# card.net
KiCad netlist of a schematic drawn in EAGLE
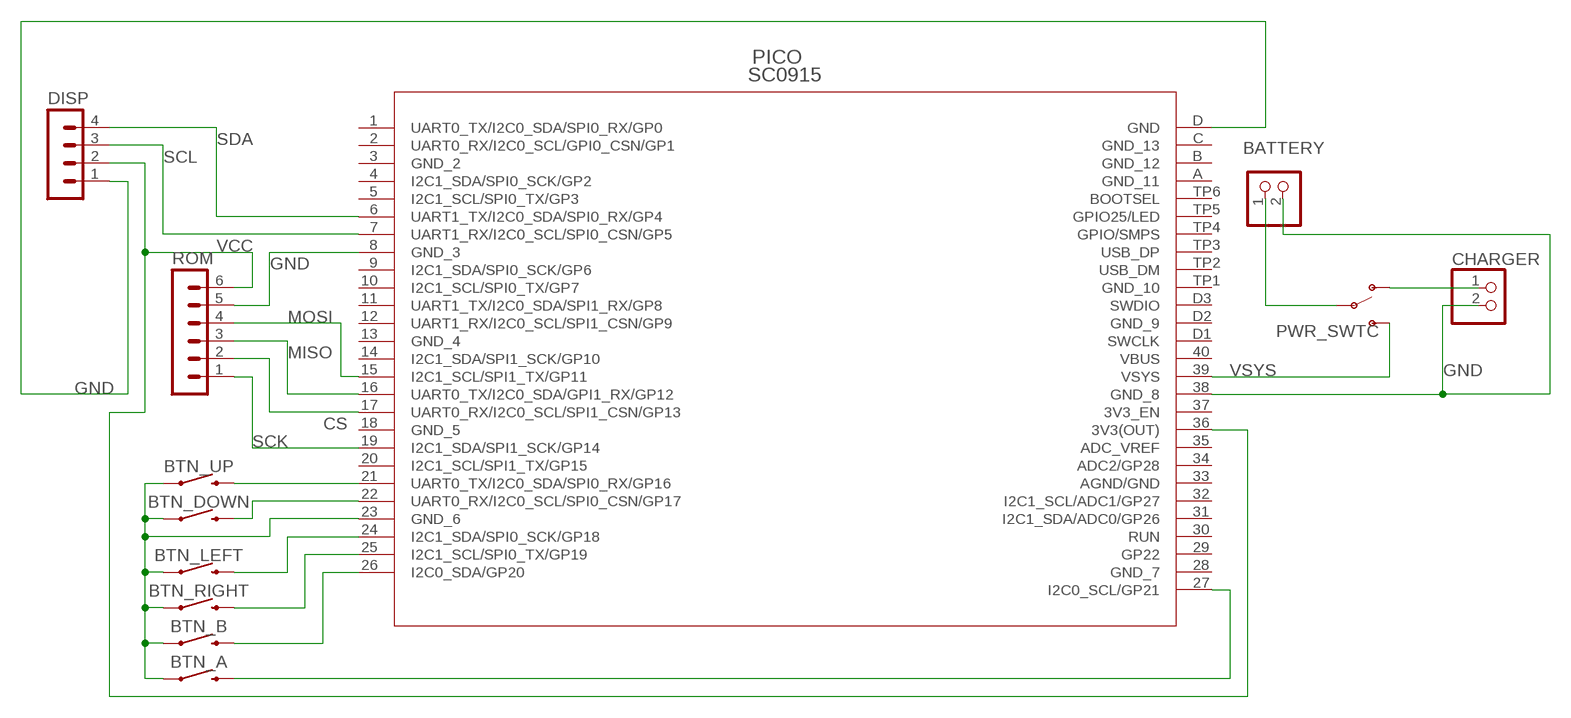
[diagram p0: schematic, sheet 1]

(export (version "E")
  (design (tool "Eeschema 10.0.6"))
  (components
    (comp (ref "BATTERY")
      (value "PINHD-1X2")
      (footprint "eagle-import:1X02")
      (libsource (lib "eagle-import") (part "PINHD-1X2"))
    )
    (comp (ref "BTN_A")
      (value "MOMENTARY-SWITCH-SPST-PTH-6.0MM")
      (footprint "eagle-import:TACTILE_SWITCH_PTH_6.0MM")
      (libsource (lib "eagle-import") (part "MOMENTARY-SWITCH-SPST-PTH-6.0MM"))
    )
    (comp (ref "BTN_B")
      (value "MOMENTARY-SWITCH-SPST-PTH-6.0MM")
      (footprint "eagle-import:TACTILE_SWITCH_PTH_6.0MM")
      (libsource (lib "eagle-import") (part "MOMENTARY-SWITCH-SPST-PTH-6.0MM"))
    )
    (comp (ref "BTN_DOWN")
      (value "MOMENTARY-SWITCH-SPST-PTH-6.0MM")
      (footprint "eagle-import:TACTILE_SWITCH_PTH_6.0MM")
      (libsource (lib "eagle-import") (part "MOMENTARY-SWITCH-SPST-PTH-6.0MM"))
    )
    (comp (ref "BTN_LEFT")
      (value "MOMENTARY-SWITCH-SPST-PTH-6.0MM")
      (footprint "eagle-import:TACTILE_SWITCH_PTH_6.0MM")
      (libsource (lib "eagle-import") (part "MOMENTARY-SWITCH-SPST-PTH-6.0MM"))
    )
    (comp (ref "BTN_RIGHT")
      (value "MOMENTARY-SWITCH-SPST-PTH-6.0MM")
      (footprint "eagle-import:TACTILE_SWITCH_PTH_6.0MM")
      (libsource (lib "eagle-import") (part "MOMENTARY-SWITCH-SPST-PTH-6.0MM"))
    )
    (comp (ref "BTN_UP")
      (value "MOMENTARY-SWITCH-SPST-PTH-6.0MM")
      (footprint "eagle-import:TACTILE_SWITCH_PTH_6.0MM")
      (libsource (lib "eagle-import") (part "MOMENTARY-SWITCH-SPST-PTH-6.0MM"))
    )
    (comp (ref "CHARGER")
      (value "PINHD-1X2")
      (footprint "eagle-import:1X02")
      (libsource (lib "eagle-import") (part "PINHD-1X2"))
    )
    (comp (ref "DISP")
      (value "MA04-1")
      (footprint "eagle-import:MA04-1")
      (libsource (lib "eagle-import") (part "MA04-1"))
    )
    (comp (ref "PICO")
      (value "SC0915")
      (footprint "eagle-import:SC0915_RPI")
      (fields (field (name "COPYRIGHT") "Copyright (C) 2018 Accelerated Designs. All rights reserved"))
      (libsource (lib "eagle-import") (part "SC0915"))
    )
    (comp (ref "PWR_SWTC")
      (value "SWITCH-SPDT-PTH-11.6X4.0MM")
      (footprint "eagle-import:SWITCH_SPDT_PTH_11.6X4.0MM")
      (libsource (lib "eagle-import") (part "SWITCH-SPDT-PTH-11.6X4.0MM"))
    )
    (comp (ref "ROM")
      (value "MA06-1")
      (footprint "eagle-import:MA06-1")
      (libsource (lib "eagle-import") (part "MA06-1"))
    )
  )
  (nets
    (net (code "1") (name "/3V3_EN") (class "Default")
      (node (ref "PICO") (pin "37") (pinfunction "3V3_EN_37") (pintype "power_in"))
    )
    (net (code "2") (name "/ADC_VREF") (class "Default")
      (node (ref "PICO") (pin "35") (pinfunction "ADC_VREF_35") (pintype "power_in"))
    )
    (net (code "3") (name "/CS") (class "Default")
      (node (ref "PICO") (pin "17") (pinfunction "UART0_RX/I2C0_SCL/SPI1_CSN/GP13_17") (pintype "bidirectional"))
      (node (ref "ROM") (pin "2") (pinfunction "2_2") (pintype "passive"))
    )
    (net (code "4") (name "/GND") (class "Default")
      (node (ref "BATTERY") (pin "2") (pinfunction "2_2") (pintype "passive"))
      (node (ref "BTN_A") (pin "1") (pinfunction "1_1") (pintype "passive"))
      (node (ref "BTN_B") (pin "1") (pinfunction "1_1") (pintype "passive"))
      (node (ref "BTN_DOWN") (pin "1") (pinfunction "1_1") (pintype "passive"))
      (node (ref "BTN_LEFT") (pin "1") (pinfunction "1_1") (pintype "passive"))
      (node (ref "BTN_RIGHT") (pin "1") (pinfunction "1_1") (pintype "passive"))
      (node (ref "BTN_UP") (pin "1") (pinfunction "1_1") (pintype "passive"))
      (node (ref "CHARGER") (pin "2") (pinfunction "2_2") (pintype "passive"))
      (node (ref "DISP") (pin "1") (pinfunction "1_1") (pintype "passive"))
      (node (ref "PICO") (pin "23") (pinfunction "GND_6_23") (pintype "passive"))
      (node (ref "PICO") (pin "38") (pinfunction "GND_8_38") (pintype "passive"))
      (node (ref "PICO") (pin "8") (pinfunction "GND_3_8") (pintype "passive"))
      (node (ref "PICO") (pin "D") (pinfunction "GND_D") (pintype "passive"))
      (node (ref "ROM") (pin "5") (pinfunction "5_5") (pintype "passive"))
    )
    (net (code "5") (name "/MISO") (class "Default")
      (node (ref "PICO") (pin "16") (pinfunction "UART0_TX/I2C0_SDA/GPI1_RX/GP12_16") (pintype "bidirectional"))
      (node (ref "ROM") (pin "3") (pinfunction "3_3") (pintype "passive"))
    )
    (net (code "6") (name "/MOSI") (class "Default")
      (node (ref "PICO") (pin "15") (pinfunction "I2C1_SCL/SPI1_TX/GP11_15") (pintype "bidirectional"))
      (node (ref "ROM") (pin "4") (pinfunction "4_4") (pintype "passive"))
    )
    (net (code "7") (name "/SCK") (class "Default")
      (node (ref "PICO") (pin "19") (pinfunction "I2C1_SDA/SPI1_SCK/GP14_19") (pintype "bidirectional"))
      (node (ref "ROM") (pin "1") (pinfunction "1_1") (pintype "passive"))
    )
    (net (code "8") (name "/SCL") (class "Default")
      (node (ref "DISP") (pin "3") (pinfunction "3_3") (pintype "passive"))
      (node (ref "PICO") (pin "7") (pinfunction "UART1_RX/I2C0_SCL/SPI0_CSN/GP5_7") (pintype "bidirectional"))
    )
    (net (code "9") (name "/SDA") (class "Default")
      (node (ref "DISP") (pin "4") (pinfunction "4_4") (pintype "passive"))
      (node (ref "PICO") (pin "6") (pinfunction "UART1_TX/I2C0_SDA/SPI0_RX/GP4_6") (pintype "bidirectional"))
    )
    (net (code "10") (name "/VBUS") (class "Default")
      (node (ref "PICO") (pin "40") (pinfunction "VBUS_40") (pintype "power_in"))
    )
    (net (code "11") (name "/VCC") (class "Default")
      (node (ref "DISP") (pin "2") (pinfunction "2_2") (pintype "passive"))
      (node (ref "PICO") (pin "36") (pinfunction "3V3(OUT)_36") (pintype "output"))
      (node (ref "ROM") (pin "6") (pinfunction "6_6") (pintype "passive"))
    )
    (net (code "12") (name "/VSYS") (class "Default")
      (node (ref "PICO") (pin "39") (pinfunction "VSYS_39") (pintype "power_in"))
      (node (ref "PWR_SWTC") (pin "3") (pinfunction "S_3") (pintype "passive"))
    )
    (net (code "13") (name "Net-(BTN_A-2)") (class "Default")
      (node (ref "BTN_A") (pin "3") (pinfunction "2_3") (pintype "passive"))
      (node (ref "PICO") (pin "27") (pinfunction "I2C0_SCL/GP21_27") (pintype "bidirectional"))
    )
    (net (code "14") (name "Net-(BTN_B-2)") (class "Default")
      (node (ref "BTN_B") (pin "3") (pinfunction "2_3") (pintype "passive"))
      (node (ref "PICO") (pin "26") (pinfunction "I2C0_SDA/GP20_26") (pintype "bidirectional"))
    )
    (net (code "15") (name "Net-(BTN_DOWN-2)") (class "Default")
      (node (ref "BTN_DOWN") (pin "3") (pinfunction "2_3") (pintype "passive"))
      (node (ref "PICO") (pin "22") (pinfunction "UART0_RX/I2C0_SCL/SPI0_CSN/GP17_22") (pintype "bidirectional"))
    )
    (net (code "16") (name "Net-(BTN_LEFT-2)") (class "Default")
      (node (ref "BTN_LEFT") (pin "3") (pinfunction "2_3") (pintype "passive"))
      (node (ref "PICO") (pin "24") (pinfunction "I2C1_SDA/SPI0_SCK/GP18_24") (pintype "bidirectional"))
    )
    (net (code "17") (name "Net-(BTN_RIGHT-2)") (class "Default")
      (node (ref "BTN_RIGHT") (pin "3") (pinfunction "2_3") (pintype "passive"))
      (node (ref "PICO") (pin "25") (pinfunction "I2C1_SCL/SPI0_TX/GP19_25") (pintype "bidirectional"))
    )
    (net (code "18") (name "Net-(BTN_UP-2)") (class "Default")
      (node (ref "BTN_UP") (pin "3") (pinfunction "2_3") (pintype "passive"))
      (node (ref "PICO") (pin "21") (pinfunction "UART0_TX/I2C0_SDA/SPI0_RX/GP16_21") (pintype "bidirectional"))
    )
    (net (code "19") (name "Net-(PWR_SWTC-O)") (class "Default")
      (node (ref "CHARGER") (pin "1") (pinfunction "1_1") (pintype "passive"))
      (node (ref "PWR_SWTC") (pin "1") (pinfunction "O_1") (pintype "passive"))
    )
    (net (code "20") (name "Net-(PWR_SWTC-P)") (class "Default")
      (node (ref "BATTERY") (pin "1") (pinfunction "1_1") (pintype "passive"))
      (node (ref "PWR_SWTC") (pin "2") (pinfunction "P_2") (pintype "passive"))
    )
    (net (code "21") (name "unconnected-(PICO-ADC2{slash}GP28-Pad34)") (class "Default")
      (node (ref "PICO") (pin "34") (pinfunction "ADC2/GP28_34") (pintype "bidirectional"))
    )
    (net (code "22") (name "unconnected-(PICO-AGND{slash}GND-Pad33)") (class "Default")
      (node (ref "PICO") (pin "33") (pinfunction "AGND/GND_33") (pintype "passive"))
    )
    (net (code "23") (name "unconnected-(PICO-BOOTSEL-PadTP6)") (class "Default")
      (node (ref "PICO") (pin "TP6") (pinfunction "BOOTSEL_TP6") (pintype "passive"))
    )
    (net (code "24") (name "unconnected-(PICO-GND_2-Pad3)") (class "Default")
      (node (ref "PICO") (pin "3") (pinfunction "GND_2_3") (pintype "passive"))
    )
    (net (code "25") (name "unconnected-(PICO-GND_4-Pad13)") (class "Default")
      (node (ref "PICO") (pin "13") (pinfunction "GND_4_13") (pintype "passive"))
    )
    (net (code "26") (name "unconnected-(PICO-GND_5-Pad18)") (class "Default")
      (node (ref "PICO") (pin "18") (pinfunction "GND_5_18") (pintype "passive"))
    )
    (net (code "27") (name "unconnected-(PICO-GND_7-Pad28)") (class "Default")
      (node (ref "PICO") (pin "28") (pinfunction "GND_7_28") (pintype "passive"))
    )
    (net (code "28") (name "unconnected-(PICO-GND_9-PadD2)") (class "Default")
      (node (ref "PICO") (pin "D2") (pinfunction "GND_9_D2") (pintype "passive"))
    )
    (net (code "29") (name "unconnected-(PICO-GND_10-PadTP1)") (class "Default")
      (node (ref "PICO") (pin "TP1") (pinfunction "GND_10_TP1") (pintype "passive"))
    )
    (net (code "30") (name "unconnected-(PICO-GND_11-PadA)") (class "Default")
      (node (ref "PICO") (pin "A") (pinfunction "GND_11_A") (pintype "passive"))
    )
    (net (code "31") (name "unconnected-(PICO-GND_12-PadB)") (class "Default")
      (node (ref "PICO") (pin "B") (pinfunction "GND_12_B") (pintype "passive"))
    )
    (net (code "32") (name "unconnected-(PICO-GND_13-PadC)") (class "Default")
      (node (ref "PICO") (pin "C") (pinfunction "GND_13_C") (pintype "passive"))
    )
    (net (code "33") (name "unconnected-(PICO-GP22-Pad29)") (class "Default")
      (node (ref "PICO") (pin "29") (pinfunction "GP22_29") (pintype "bidirectional"))
    )
    (net (code "34") (name "unconnected-(PICO-GPIO25{slash}LED-PadTP5)") (class "Default")
      (node (ref "PICO") (pin "TP5") (pinfunction "GPIO25/LED_TP5") (pintype "passive"))
    )
    (net (code "35") (name "unconnected-(PICO-GPIO{slash}SMPS-PadTP4)") (class "Default")
      (node (ref "PICO") (pin "TP4") (pinfunction "GPIO/SMPS_TP4") (pintype "passive"))
    )
    (net (code "36") (name "unconnected-(PICO-I2C1_SCL{slash}ADC1{slash}GP27-Pad32)") (class "Default")
      (node (ref "PICO") (pin "32") (pinfunction "I2C1_SCL/ADC1/GP27_32") (pintype "bidirectional"))
    )
    (net (code "37") (name "unconnected-(PICO-I2C1_SCL{slash}SPI0_TX{slash}GP3-Pad5)") (class "Default")
      (node (ref "PICO") (pin "5") (pinfunction "I2C1_SCL/SPI0_TX/GP3_5") (pintype "bidirectional"))
    )
    (net (code "38") (name "unconnected-(PICO-I2C1_SCL{slash}SPI0_TX{slash}GP7-Pad10)") (class "Default")
      (node (ref "PICO") (pin "10") (pinfunction "I2C1_SCL/SPI0_TX/GP7_10") (pintype "bidirectional"))
    )
    (net (code "39") (name "unconnected-(PICO-I2C1_SCL{slash}SPI1_TX{slash}GP15-Pad20)") (class "Default")
      (node (ref "PICO") (pin "20") (pinfunction "I2C1_SCL/SPI1_TX/GP15_20") (pintype "bidirectional"))
    )
    (net (code "40") (name "unconnected-(PICO-I2C1_SDA{slash}ADC0{slash}GP26-Pad31)") (class "Default")
      (node (ref "PICO") (pin "31") (pinfunction "I2C1_SDA/ADC0/GP26_31") (pintype "bidirectional"))
    )
    (net (code "41") (name "unconnected-(PICO-I2C1_SDA{slash}SPI0_SCK{slash}GP2-Pad4)") (class "Default")
      (node (ref "PICO") (pin "4") (pinfunction "I2C1_SDA/SPI0_SCK/GP2_4") (pintype "bidirectional"))
    )
    (net (code "42") (name "unconnected-(PICO-I2C1_SDA{slash}SPI0_SCK{slash}GP6-Pad9)") (class "Default")
      (node (ref "PICO") (pin "9") (pinfunction "I2C1_SDA/SPI0_SCK/GP6_9") (pintype "bidirectional"))
    )
    (net (code "43") (name "unconnected-(PICO-I2C1_SDA{slash}SPI1_SCK{slash}GP10-Pad14)") (class "Default")
      (node (ref "PICO") (pin "14") (pinfunction "I2C1_SDA/SPI1_SCK/GP10_14") (pintype "bidirectional"))
    )
    (net (code "44") (name "unconnected-(PICO-RUN-Pad30)") (class "Default")
      (node (ref "PICO") (pin "30") (pinfunction "RUN_30") (pintype "passive"))
    )
    (net (code "45") (name "unconnected-(PICO-SWCLK-PadD1)") (class "Default")
      (node (ref "PICO") (pin "D1") (pinfunction "SWCLK_D1") (pintype "passive"))
    )
    (net (code "46") (name "unconnected-(PICO-SWDIO-PadD3)") (class "Default")
      (node (ref "PICO") (pin "D3") (pinfunction "SWDIO_D3") (pintype "passive"))
    )
    (net (code "47") (name "unconnected-(PICO-UART0_RX{slash}I2C0_SCL{slash}GPI0_CSN{slash}GP1-Pad2)") (class "Default")
      (node (ref "PICO") (pin "2") (pinfunction "UART0_RX/I2C0_SCL/GPI0_CSN/GP1_2") (pintype "bidirectional"))
    )
    (net (code "48") (name "unconnected-(PICO-UART0_TX{slash}I2C0_SDA{slash}SPI0_RX{slash}GP0-Pad1)") (class "Default")
      (node (ref "PICO") (pin "1") (pinfunction "UART0_TX/I2C0_SDA/SPI0_RX/GP0_1") (pintype "bidirectional"))
    )
    (net (code "49") (name "unconnected-(PICO-UART1_RX{slash}I2C0_SCL{slash}SPI1_CSN{slash}GP9-Pad12)") (class "Default")
      (node (ref "PICO") (pin "12") (pinfunction "UART1_RX/I2C0_SCL/SPI1_CSN/GP9_12") (pintype "bidirectional"))
    )
    (net (code "50") (name "unconnected-(PICO-UART1_TX{slash}I2C0_SDA{slash}SPI1_RX{slash}GP8-Pad11)") (class "Default")
      (node (ref "PICO") (pin "11") (pinfunction "UART1_TX/I2C0_SDA/SPI1_RX/GP8_11") (pintype "bidirectional"))
    )
    (net (code "51") (name "unconnected-(PICO-USB_DM-PadTP2)") (class "Default")
      (node (ref "PICO") (pin "TP2") (pinfunction "USB_DM_TP2") (pintype "passive"))
    )
    (net (code "52") (name "unconnected-(PICO-USB_DP-PadTP3)") (class "Default")
      (node (ref "PICO") (pin "TP3") (pinfunction "USB_DP_TP3") (pintype "passive"))
    )
  )
)
